# PCB_2_3.net
KiCad netlist of a schematic drawn in EAGLE
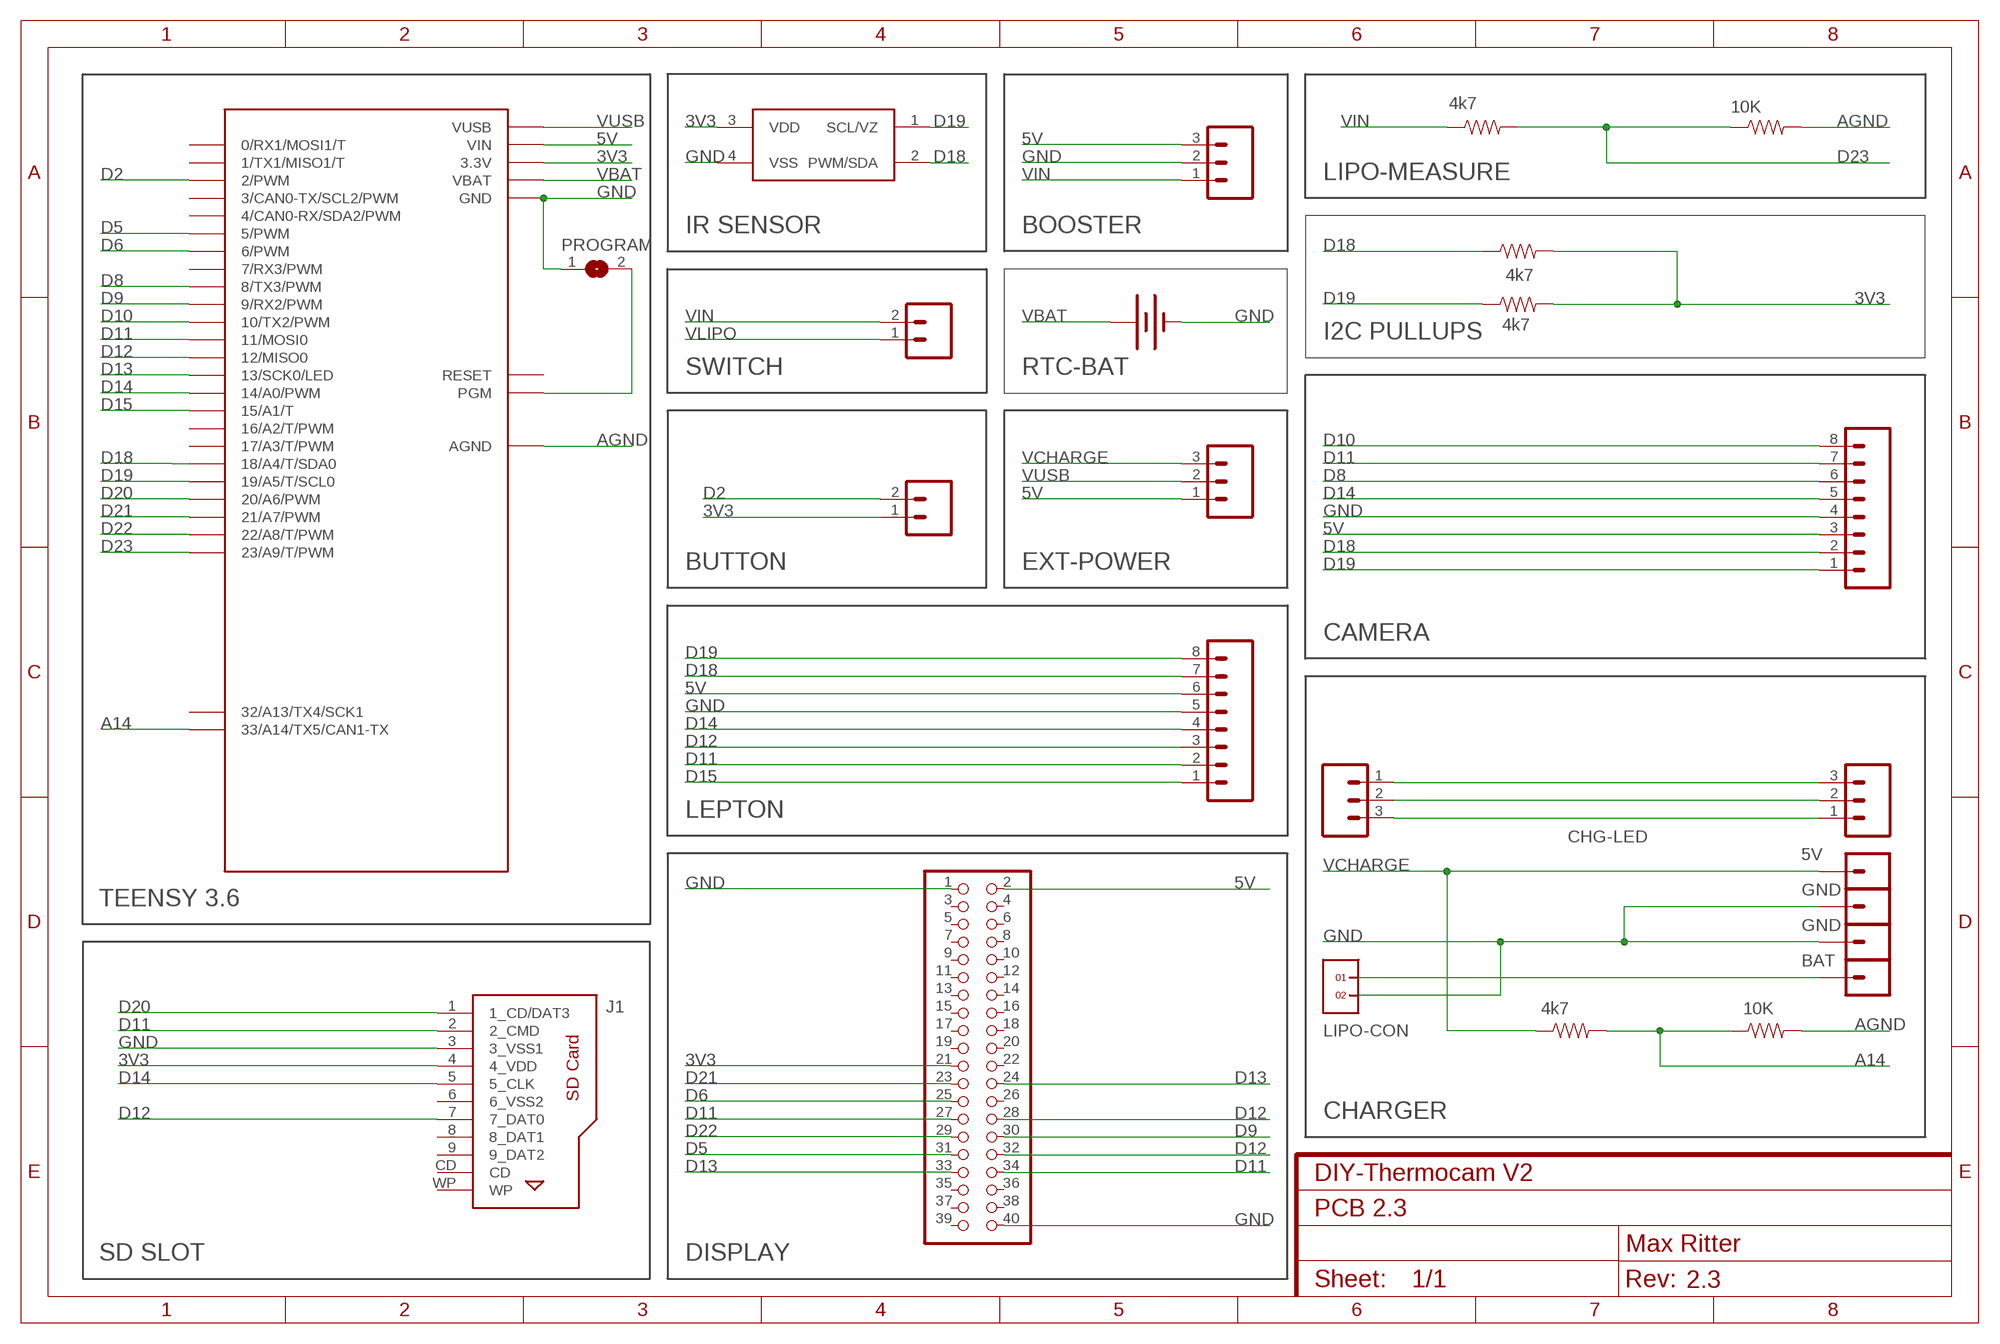
[diagram p0: schematic, sheet 1]

(export (version "E")
  (design (tool "Eeschema 10.0.6"))
  (components
    (comp (ref "BAT")
      (value "BATTERY12PTH")
      (footprint "eagle-import:BATTCON_12MM_PTH")
      (libsource (lib "eagle-import") (part "BATTERY12PTH"))
    )
    (comp (ref "BOOSTER")
      (value "M03PTH")
      (footprint "eagle-import:1X03")
      (libsource (lib "eagle-import") (part "M03PTH"))
    )
    (comp (ref "BUTTON")
      (value "M02PTH")
      (footprint "eagle-import:1X02")
      (libsource (lib "eagle-import") (part "M02PTH"))
    )
    (comp (ref "CHG-LED")
      (value "M03PTH")
      (footprint "eagle-import:1X03")
      (libsource (lib "eagle-import") (part "M03PTH"))
    )
    (comp (ref "EXT-POWER")
      (value "M03PTH")
      (footprint "eagle-import:1X03")
      (libsource (lib "eagle-import") (part "M03PTH"))
    )
    (comp (ref "J1")
      (value "693063020911")
      (footprint "eagle-import:693063020911")
      (libsource (lib "eagle-import") (part "693063020911"))
    )
    (comp (ref "JP1")
      (value "M01PTH")
      (footprint "eagle-import:1X01")
      (libsource (lib "eagle-import") (part "M01PTH"))
    )
    (comp (ref "JP2")
      (value "M01PTH")
      (footprint "eagle-import:1X01")
      (libsource (lib "eagle-import") (part "M01PTH"))
    )
    (comp (ref "JP3")
      (value "M01PTH")
      (footprint "eagle-import:1X01")
      (libsource (lib "eagle-import") (part "M01PTH"))
    )
    (comp (ref "JP4")
      (value "M01PTH")
      (footprint "eagle-import:1X01")
      (libsource (lib "eagle-import") (part "M01PTH"))
    )
    (comp (ref "LASER1")
      (value "M03PTH")
      (footprint "eagle-import:1X03")
      (libsource (lib "eagle-import") (part "M03PTH"))
    )
    (comp (ref "LCD-HEADER")
      (value "PINHD-2X20")
      (footprint "eagle-import:2X20")
      (libsource (lib "eagle-import") (part "PINHD-2X20"))
    )
    (comp (ref "LEPTON_MODULE")
      (value "M08")
      (footprint "eagle-import:1X08_ROUND")
      (libsource (lib "eagle-import") (part "M08"))
    )
    (comp (ref "LEPTON_MODULE1")
      (value "M08")
      (footprint "eagle-import:1X08_ROUND")
      (libsource (lib "eagle-import") (part "M08"))
    )
    (comp (ref "LIPO-CON")
      (value "1X2")
      (footprint "eagle-import:1X2")
      (libsource (lib "eagle-import") (part "1X2"))
    )
    (comp (ref "PROGRAM")
      (value "SJ")
      (footprint "eagle-import:SJ")
      (libsource (lib "eagle-import") (part "SJ"))
    )
    (comp (ref "R1")
      (value "4k7")
      (footprint "eagle-import:AXIAL-0.4")
      (libsource (lib "eagle-import") (part "RESISTORPTH-1/4W"))
    )
    (comp (ref "R2")
      (value "10K")
      (footprint "eagle-import:AXIAL-0.4")
      (libsource (lib "eagle-import") (part "RESISTORPTH-1/4W"))
    )
    (comp (ref "R3")
      (value "4k7")
      (footprint "eagle-import:AXIAL-0.4")
      (libsource (lib "eagle-import") (part "RESISTORPTH-1/4W"))
    )
    (comp (ref "R4")
      (value "4k7")
      (footprint "eagle-import:AXIAL-0.4")
      (libsource (lib "eagle-import") (part "RESISTORPTH-1/4W"))
    )
    (comp (ref "R5")
      (value "10K")
      (footprint "eagle-import:AXIAL-0.4")
      (libsource (lib "eagle-import") (part "RESISTORPTH-1/4W"))
    )
    (comp (ref "R6")
      (value "4k7")
      (footprint "eagle-import:AXIAL-0.4")
      (libsource (lib "eagle-import") (part "RESISTORPTH-1/4W"))
    )
    (comp (ref "SWITCH")
      (value "M02PTH")
      (footprint "eagle-import:1X02")
      (libsource (lib "eagle-import") (part "M02PTH"))
    )
    (comp (ref "U$1")
      (value "TEENSY_3.6_ALL_PINS")
      (footprint "eagle-import:TEENSY_3.6_ALL_PINS")
      (libsource (lib "eagle-import") (part "TEENSY_3.6_ALL_PINS"))
    )
    (comp (ref "U1")
      (value "MLX90614_")
      (footprint "eagle-import:TO-39")
      (libsource (lib "eagle-import") (part "MLX90614_"))
    )
  )
  (nets
    (net (code "1") (name "/3V3") (class "Default")
      (node (ref "BUTTON") (pin "1") (pinfunction "1_1") (pintype "passive"))
      (node (ref "J1") (pin "4") (pinfunction "4_VDD_4") (pintype "bidirectional"))
      (node (ref "LCD-HEADER") (pin "21") (pinfunction "21_21") (pintype "passive"))
      (node (ref "R4") (pin "P$2") (pinfunction "2_P$2") (pintype "passive"))
      (node (ref "R6") (pin "P$2") (pinfunction "2_P$2") (pintype "passive"))
      (node (ref "U$1") (pin "3.3V") (pinfunction "3.3V_3.3V") (pintype "power_in"))
      (node (ref "U$1") (pin "3.3V3") (pinfunction "3.3V_3.3V3") (pintype "power_in"))
      (node (ref "U$1") (pin "3.3V4") (pinfunction "3.3V_3.3V4") (pintype "power_in"))
      (node (ref "U1") (pin "3") (pinfunction "VDD_3") (pintype "bidirectional"))
    )
    (net (code "2") (name "/5V") (class "Default")
      (node (ref "BOOSTER") (pin "3") (pinfunction "3_3") (pintype "passive"))
      (node (ref "EXT-POWER") (pin "1") (pinfunction "1_1") (pintype "passive"))
      (node (ref "LCD-HEADER") (pin "2") (pinfunction "2_2") (pintype "passive"))
      (node (ref "LEPTON_MODULE") (pin "6") (pinfunction "6_6") (pintype "passive"))
      (node (ref "LEPTON_MODULE1") (pin "3") (pinfunction "3_3") (pintype "passive"))
      (node (ref "U$1") (pin "VIN") (pinfunction "VIN_VIN") (pintype "power_in"))
    )
    (net (code "3") (name "/A14") (class "Default")
      (node (ref "R3") (pin "P$2") (pinfunction "2_P$2") (pintype "passive"))
      (node (ref "R5") (pin "P$1") (pinfunction "1_P$1") (pintype "passive"))
      (node (ref "U$1") (pin "33/A14") (pinfunction "33/A14/TX5/CAN1-TX_33/A14") (pintype "bidirectional"))
    )
    (net (code "4") (name "/AGND") (class "Default")
      (node (ref "R2") (pin "P$2") (pinfunction "2_P$2") (pintype "passive"))
      (node (ref "R5") (pin "P$2") (pinfunction "2_P$2") (pintype "passive"))
      (node (ref "U$1") (pin "AGND") (pinfunction "AGND_AGND") (pintype "power_in"))
    )
    (net (code "5") (name "/D2") (class "Default")
      (node (ref "BUTTON") (pin "2") (pinfunction "2_2") (pintype "passive"))
      (node (ref "U$1") (pin "2") (pinfunction "2/PWM_2") (pintype "bidirectional"))
    )
    (net (code "6") (name "/D5") (class "Default")
      (node (ref "LCD-HEADER") (pin "31") (pinfunction "31_31") (pintype "passive"))
      (node (ref "U$1") (pin "5") (pinfunction "5/PWM_5") (pintype "bidirectional"))
    )
    (net (code "7") (name "/D6") (class "Default")
      (node (ref "LCD-HEADER") (pin "25") (pinfunction "25_25") (pintype "passive"))
      (node (ref "U$1") (pin "6") (pinfunction "6/PWM_6") (pintype "bidirectional"))
    )
    (net (code "8") (name "/D8") (class "Default")
      (node (ref "LEPTON_MODULE1") (pin "6") (pinfunction "6_6") (pintype "passive"))
      (node (ref "U$1") (pin "8") (pinfunction "8/TX3/PWM_8") (pintype "bidirectional"))
    )
    (net (code "9") (name "/D9") (class "Default")
      (node (ref "LCD-HEADER") (pin "30") (pinfunction "30_30") (pintype "passive"))
      (node (ref "U$1") (pin "9") (pinfunction "9/RX2/PWM_9") (pintype "bidirectional"))
    )
    (net (code "10") (name "/D10") (class "Default")
      (node (ref "LEPTON_MODULE1") (pin "8") (pinfunction "8_8") (pintype "passive"))
      (node (ref "U$1") (pin "10") (pinfunction "10/TX2/PWM_10") (pintype "bidirectional"))
    )
    (net (code "11") (name "/D11") (class "Default")
      (node (ref "J1") (pin "2") (pinfunction "2_CMD_2") (pintype "bidirectional"))
      (node (ref "LCD-HEADER") (pin "27") (pinfunction "27_27") (pintype "passive"))
      (node (ref "LCD-HEADER") (pin "34") (pinfunction "34_34") (pintype "passive"))
      (node (ref "LEPTON_MODULE") (pin "2") (pinfunction "2_2") (pintype "passive"))
      (node (ref "LEPTON_MODULE1") (pin "7") (pinfunction "7_7") (pintype "passive"))
      (node (ref "U$1") (pin "11") (pinfunction "11/MOSI0_11") (pintype "bidirectional"))
    )
    (net (code "12") (name "/D12") (class "Default")
      (node (ref "J1") (pin "7") (pinfunction "7_DAT0_7") (pintype "bidirectional"))
      (node (ref "LCD-HEADER") (pin "28") (pinfunction "28_28") (pintype "passive"))
      (node (ref "LCD-HEADER") (pin "32") (pinfunction "32_32") (pintype "passive"))
      (node (ref "LEPTON_MODULE") (pin "3") (pinfunction "3_3") (pintype "passive"))
      (node (ref "U$1") (pin "12") (pinfunction "12/MISO0_12") (pintype "bidirectional"))
    )
    (net (code "13") (name "/D13") (class "Default")
      (node (ref "LCD-HEADER") (pin "24") (pinfunction "24_24") (pintype "passive"))
      (node (ref "LCD-HEADER") (pin "33") (pinfunction "33_33") (pintype "passive"))
      (node (ref "U$1") (pin "13") (pinfunction "13/SCK0/LED_13") (pintype "bidirectional"))
    )
    (net (code "14") (name "/D14") (class "Default")
      (node (ref "J1") (pin "5") (pinfunction "5_CLK_5") (pintype "bidirectional"))
      (node (ref "LEPTON_MODULE") (pin "4") (pinfunction "4_4") (pintype "passive"))
      (node (ref "LEPTON_MODULE1") (pin "5") (pinfunction "5_5") (pintype "passive"))
      (node (ref "U$1") (pin "14/A0") (pinfunction "14/A0/PWM_14/A0") (pintype "bidirectional"))
    )
    (net (code "15") (name "/D15") (class "Default")
      (node (ref "LEPTON_MODULE") (pin "1") (pinfunction "1_1") (pintype "passive"))
      (node (ref "U$1") (pin "15/A1") (pinfunction "15/A1/T_15/A1") (pintype "bidirectional"))
    )
    (net (code "16") (name "/D18") (class "Default")
      (node (ref "LEPTON_MODULE") (pin "7") (pinfunction "7_7") (pintype "passive"))
      (node (ref "LEPTON_MODULE1") (pin "2") (pinfunction "2_2") (pintype "passive"))
      (node (ref "R4") (pin "P$1") (pinfunction "1_P$1") (pintype "passive"))
      (node (ref "U$1") (pin "18/A4") (pinfunction "18/A4/T/SDA0_18/A4") (pintype "bidirectional"))
      (node (ref "U1") (pin "2") (pinfunction "PWM/SDA_2") (pintype "bidirectional"))
    )
    (net (code "17") (name "/D19") (class "Default")
      (node (ref "LEPTON_MODULE") (pin "8") (pinfunction "8_8") (pintype "passive"))
      (node (ref "LEPTON_MODULE1") (pin "1") (pinfunction "1_1") (pintype "passive"))
      (node (ref "R6") (pin "P$1") (pinfunction "1_P$1") (pintype "passive"))
      (node (ref "U$1") (pin "19/A5") (pinfunction "19/A5/T/SCL0_19/A5") (pintype "bidirectional"))
      (node (ref "U1") (pin "1") (pinfunction "SCL/VZ_1") (pintype "bidirectional"))
    )
    (net (code "18") (name "/D20") (class "Default")
      (node (ref "J1") (pin "1") (pinfunction "1_CD/DAT3_1") (pintype "bidirectional"))
      (node (ref "U$1") (pin "20/A6") (pinfunction "20/A6/PWM_20/A6") (pintype "bidirectional"))
    )
    (net (code "19") (name "/D21") (class "Default")
      (node (ref "LCD-HEADER") (pin "23") (pinfunction "23_23") (pintype "passive"))
      (node (ref "U$1") (pin "21/A7") (pinfunction "21/A7/PWM_21/A7") (pintype "bidirectional"))
    )
    (net (code "20") (name "/D22") (class "Default")
      (node (ref "LCD-HEADER") (pin "29") (pinfunction "29_29") (pintype "passive"))
      (node (ref "U$1") (pin "22/A8") (pinfunction "22/A8/T/PWM_22/A8") (pintype "bidirectional"))
    )
    (net (code "21") (name "/D23") (class "Default")
      (node (ref "R1") (pin "P$2") (pinfunction "2_P$2") (pintype "passive"))
      (node (ref "R2") (pin "P$1") (pinfunction "1_P$1") (pintype "passive"))
      (node (ref "U$1") (pin "23/A9") (pinfunction "23/A9/T/PWM_23/A9") (pintype "bidirectional"))
    )
    (net (code "22") (name "/GND") (class "Default")
      (node (ref "BAT") (pin "GND") (pinfunction "-_GND") (pintype "power_in"))
      (node (ref "BOOSTER") (pin "2") (pinfunction "2_2") (pintype "passive"))
      (node (ref "J1") (pin "3") (pinfunction "3_VSS1_3") (pintype "bidirectional"))
      (node (ref "JP1") (pin "1") (pinfunction "1_1") (pintype "passive"))
      (node (ref "JP2") (pin "1") (pinfunction "1_1") (pintype "passive"))
      (node (ref "LCD-HEADER") (pin "1") (pinfunction "1_1") (pintype "passive"))
      (node (ref "LCD-HEADER") (pin "40") (pinfunction "40_40") (pintype "passive"))
      (node (ref "LEPTON_MODULE") (pin "5") (pinfunction "5_5") (pintype "passive"))
      (node (ref "LEPTON_MODULE1") (pin "4") (pinfunction "4_4") (pintype "passive"))
      (node (ref "LIPO-CON") (pin "2") (pinfunction "2_2") (pintype "bidirectional"))
      (node (ref "PROGRAM") (pin "1") (pinfunction "1_1") (pintype "passive"))
      (node (ref "U$1") (pin "GND") (pinfunction "GND_GND") (pintype "power_in"))
      (node (ref "U$1") (pin "GND1") (pinfunction "GND_GND1") (pintype "power_in"))
      (node (ref "U$1") (pin "GND6") (pinfunction "GND_GND6") (pintype "power_in"))
      (node (ref "U1") (pin "4") (pinfunction "VSS_4") (pintype "bidirectional"))
    )
    (net (code "23") (name "/VBAT") (class "Default")
      (node (ref "BAT") (pin "VCC@1") (pinfunction "+_VCC@1") (pintype "power_in"))
      (node (ref "U$1") (pin "VBAT") (pinfunction "VBAT_VBAT") (pintype "power_in"))
    )
    (net (code "24") (name "/VCHARGE") (class "Default")
      (node (ref "EXT-POWER") (pin "3") (pinfunction "3_3") (pintype "passive"))
      (node (ref "JP4") (pin "1") (pinfunction "1_1") (pintype "passive"))
      (node (ref "R3") (pin "P$1") (pinfunction "1_P$1") (pintype "passive"))
    )
    (net (code "25") (name "/VIN") (class "Default")
      (node (ref "BOOSTER") (pin "1") (pinfunction "1_1") (pintype "passive"))
      (node (ref "R1") (pin "P$1") (pinfunction "1_P$1") (pintype "passive"))
      (node (ref "SWITCH") (pin "2") (pinfunction "2_2") (pintype "passive"))
    )
    (net (code "26") (name "/VLIPO") (class "Default")
      (node (ref "JP3") (pin "1") (pinfunction "1_1") (pintype "passive"))
      (node (ref "LIPO-CON") (pin "1") (pinfunction "1_1") (pintype "bidirectional"))
      (node (ref "SWITCH") (pin "1") (pinfunction "1_1") (pintype "passive"))
    )
    (net (code "27") (name "/VUSB") (class "Default")
      (node (ref "EXT-POWER") (pin "2") (pinfunction "2_2") (pintype "passive"))
      (node (ref "U$1") (pin "VUSB") (pinfunction "VUSB_VUSB") (pintype "power_in"))
    )
    (net (code "28") (name "Net-(CHG-LED-Pad1)") (class "Default")
      (node (ref "CHG-LED") (pin "1") (pinfunction "1_1") (pintype "passive"))
      (node (ref "LASER1") (pin "3") (pinfunction "3_3") (pintype "passive"))
    )
    (net (code "29") (name "Net-(CHG-LED-Pad2)") (class "Default")
      (node (ref "CHG-LED") (pin "2") (pinfunction "2_2") (pintype "passive"))
      (node (ref "LASER1") (pin "2") (pinfunction "2_2") (pintype "passive"))
    )
    (net (code "30") (name "Net-(CHG-LED-Pad3)") (class "Default")
      (node (ref "CHG-LED") (pin "3") (pinfunction "3_3") (pintype "passive"))
      (node (ref "LASER1") (pin "1") (pinfunction "1_1") (pintype "passive"))
    )
    (net (code "31") (name "Net-(PROGRAM-Pad2)") (class "Default")
      (node (ref "PROGRAM") (pin "2") (pinfunction "2_2") (pintype "passive"))
      (node (ref "U$1") (pin "PGM") (pinfunction "PGM_PGM") (pintype "bidirectional"))
    )
    (net (code "32") (name "unconnected-(J1-6_VSS2-Pad6)") (class "Default")
      (node (ref "J1") (pin "6") (pinfunction "6_VSS2_6") (pintype "bidirectional"))
    )
    (net (code "33") (name "unconnected-(J1-8_DAT1-Pad8)") (class "Default")
      (node (ref "J1") (pin "8") (pinfunction "8_DAT1_8") (pintype "bidirectional"))
    )
    (net (code "34") (name "unconnected-(J1-9_DAT2-Pad9)") (class "Default")
      (node (ref "J1") (pin "9") (pinfunction "9_DAT2_9") (pintype "bidirectional"))
    )
    (net (code "35") (name "unconnected-(J1-PadCD)") (class "Default")
      (node (ref "J1") (pin "CD") (pinfunction "CD_CD") (pintype "bidirectional"))
    )
    (net (code "36") (name "unconnected-(J1-PadWP)") (class "Default")
      (node (ref "J1") (pin "WP") (pinfunction "WP_WP") (pintype "bidirectional"))
    )
    (net (code "37") (name "unconnected-(LCD-HEADER-Pad3)") (class "Default")
      (node (ref "LCD-HEADER") (pin "3") (pinfunction "3_3") (pintype "passive"))
    )
    (net (code "38") (name "unconnected-(LCD-HEADER-Pad4)") (class "Default")
      (node (ref "LCD-HEADER") (pin "4") (pinfunction "4_4") (pintype "passive"))
    )
    (net (code "39") (name "unconnected-(LCD-HEADER-Pad5)") (class "Default")
      (node (ref "LCD-HEADER") (pin "5") (pinfunction "5_5") (pintype "passive"))
    )
    (net (code "40") (name "unconnected-(LCD-HEADER-Pad6)") (class "Default")
      (node (ref "LCD-HEADER") (pin "6") (pinfunction "6_6") (pintype "passive"))
    )
    (net (code "41") (name "unconnected-(LCD-HEADER-Pad7)") (class "Default")
      (node (ref "LCD-HEADER") (pin "7") (pinfunction "7_7") (pintype "passive"))
    )
    (net (code "42") (name "unconnected-(LCD-HEADER-Pad8)") (class "Default")
      (node (ref "LCD-HEADER") (pin "8") (pinfunction "8_8") (pintype "passive"))
    )
    (net (code "43") (name "unconnected-(LCD-HEADER-Pad9)") (class "Default")
      (node (ref "LCD-HEADER") (pin "9") (pinfunction "9_9") (pintype "passive"))
    )
    (net (code "44") (name "unconnected-(LCD-HEADER-Pad10)") (class "Default")
      (node (ref "LCD-HEADER") (pin "10") (pinfunction "10_10") (pintype "passive"))
    )
    (net (code "45") (name "unconnected-(LCD-HEADER-Pad11)") (class "Default")
      (node (ref "LCD-HEADER") (pin "11") (pinfunction "11_11") (pintype "passive"))
    )
    (net (code "46") (name "unconnected-(LCD-HEADER-Pad12)") (class "Default")
      (node (ref "LCD-HEADER") (pin "12") (pinfunction "12_12") (pintype "passive"))
    )
    (net (code "47") (name "unconnected-(LCD-HEADER-Pad13)") (class "Default")
      (node (ref "LCD-HEADER") (pin "13") (pinfunction "13_13") (pintype "passive"))
    )
    (net (code "48") (name "unconnected-(LCD-HEADER-Pad14)") (class "Default")
      (node (ref "LCD-HEADER") (pin "14") (pinfunction "14_14") (pintype "passive"))
    )
    (net (code "49") (name "unconnected-(LCD-HEADER-Pad15)") (class "Default")
      (node (ref "LCD-HEADER") (pin "15") (pinfunction "15_15") (pintype "passive"))
    )
    (net (code "50") (name "unconnected-(LCD-HEADER-Pad16)") (class "Default")
      (node (ref "LCD-HEADER") (pin "16") (pinfunction "16_16") (pintype "passive"))
    )
    (net (code "51") (name "unconnected-(LCD-HEADER-Pad17)") (class "Default")
      (node (ref "LCD-HEADER") (pin "17") (pinfunction "17_17") (pintype "passive"))
    )
    (net (code "52") (name "unconnected-(LCD-HEADER-Pad18)") (class "Default")
      (node (ref "LCD-HEADER") (pin "18") (pinfunction "18_18") (pintype "passive"))
    )
    (net (code "53") (name "unconnected-(LCD-HEADER-Pad19)") (class "Default")
      (node (ref "LCD-HEADER") (pin "19") (pinfunction "19_19") (pintype "passive"))
    )
    (net (code "54") (name "unconnected-(LCD-HEADER-Pad20)") (class "Default")
      (node (ref "LCD-HEADER") (pin "20") (pinfunction "20_20") (pintype "passive"))
    )
    (net (code "55") (name "unconnected-(LCD-HEADER-Pad22)") (class "Default")
      (node (ref "LCD-HEADER") (pin "22") (pinfunction "22_22") (pintype "passive"))
    )
    (net (code "56") (name "unconnected-(LCD-HEADER-Pad26)") (class "Default")
      (node (ref "LCD-HEADER") (pin "26") (pinfunction "26_26") (pintype "passive"))
    )
    (net (code "57") (name "unconnected-(LCD-HEADER-Pad35)") (class "Default")
      (node (ref "LCD-HEADER") (pin "35") (pinfunction "35_35") (pintype "passive"))
    )
    (net (code "58") (name "unconnected-(LCD-HEADER-Pad36)") (class "Default")
      (node (ref "LCD-HEADER") (pin "36") (pinfunction "36_36") (pintype "passive"))
    )
    (net (code "59") (name "unconnected-(LCD-HEADER-Pad37)") (class "Default")
      (node (ref "LCD-HEADER") (pin "37") (pinfunction "37_37") (pintype "passive"))
    )
    (net (code "60") (name "unconnected-(LCD-HEADER-Pad38)") (class "Default")
      (node (ref "LCD-HEADER") (pin "38") (pinfunction "38_38") (pintype "passive"))
    )
    (net (code "61") (name "unconnected-(LCD-HEADER-Pad39)") (class "Default")
      (node (ref "LCD-HEADER") (pin "39") (pinfunction "39_39") (pintype "passive"))
    )
    (net (code "62") (name "unconnected-(U$1-0{slash}RX1{slash}MOSI1{slash}T-Pad0)") (class "Default")
      (node (ref "U$1") (pin "0") (pinfunction "0/RX1/MOSI1/T_0") (pintype "bidirectional"))
    )
    (net (code "63") (name "unconnected-(U$1-1{slash}TX1{slash}MISO1{slash}T-Pad1)") (class "Default")
      (node (ref "U$1") (pin "1") (pinfunction "1/TX1/MISO1/T_1") (pintype "bidirectional"))
    )
    (net (code "64") (name "unconnected-(U$1-3{slash}CAN0-TX{slash}SCL2{slash}PWM-Pad3)") (class "Default")
      (node (ref "U$1") (pin "3") (pinfunction "3/CAN0-TX/SCL2/PWM_3") (pintype "bidirectional"))
    )
    (net (code "65") (name "unconnected-(U$1-4{slash}CAN0-RX{slash}SDA2{slash}PWM-Pad4)") (class "Default")
      (node (ref "U$1") (pin "4") (pinfunction "4/CAN0-RX/SDA2/PWM_4") (pintype "bidirectional"))
    )
    (net (code "66") (name "unconnected-(U$1-7{slash}RX3{slash}PWM-Pad7)") (class "Default")
      (node (ref "U$1") (pin "7") (pinfunction "7/RX3/PWM_7") (pintype "bidirectional"))
    )
    (net (code "67") (name "unconnected-(U$1-16{slash}A2{slash}T{slash}PWM-Pad16{slash}A2)") (class "Default")
      (node (ref "U$1") (pin "16/A2") (pinfunction "16/A2/T/PWM_16/A2") (pintype "bidirectional"))
    )
    (net (code "68") (name "unconnected-(U$1-17{slash}A3{slash}T{slash}PWM-Pad17{slash}A3)") (class "Default")
      (node (ref "U$1") (pin "17/A3") (pinfunction "17/A3/T/PWM_17/A3") (pintype "bidirectional"))
    )
    (net (code "69") (name "unconnected-(U$1-32{slash}A13{slash}TX4{slash}SCK1-Pad32{slash}A13)") (class "Default")
      (node (ref "U$1") (pin "32/A13") (pinfunction "32/A13/TX4/SCK1_32/A13") (pintype "bidirectional"))
    )
    (net (code "70") (name "unconnected-(U$1-PadRESET)") (class "Default")
      (node (ref "U$1") (pin "RESET") (pinfunction "RESET_RESET") (pintype "bidirectional"))
    )
  )
)
